# encoder.net
KiCad netlist of a schematic drawn in EAGLE
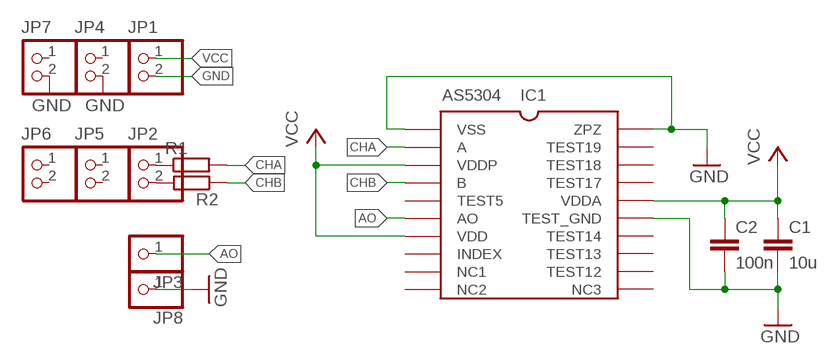
[diagram p0: schematic, sheet 1]

(export (version "E")
  (design (tool "Eeschema 10.0.6"))
  (components
    (comp (ref "C1")
      (value "10u")
      (footprint "eagle-import:C0603")
      (libsource (lib "eagle-import") (part "C-EUC0603"))
    )
    (comp (ref "C2")
      (value "100n")
      (footprint "eagle-import:C0603")
      (libsource (lib "eagle-import") (part "C-EUC0603"))
    )
    (comp (ref "IC1")
      (value "AS5304")
      (footprint "eagle-import:TSSOP20")
      (libsource (lib "eagle-import") (part "AS5304"))
    )
    (comp (ref "JP1")
      (value "PINHD_1X2_ROUND")
      (footprint "eagle-import:PINHD_1X2_ROUND")
      (libsource (lib "eagle-import") (part "PINHD_1X2_ROUND"))
    )
    (comp (ref "JP2")
      (value "PINHD_1X2_ROUND")
      (footprint "eagle-import:PINHD_1X2_ROUND")
      (libsource (lib "eagle-import") (part "PINHD_1X2_ROUND"))
    )
    (comp (ref "JP3")
      (value "PINHD-1X1")
      (footprint "eagle-import:1X01")
      (libsource (lib "eagle-import") (part "PINHD-1X1"))
    )
    (comp (ref "JP4")
      (value "PINHD_1X2_ROUND")
      (footprint "eagle-import:PINHD_1X2_ROUND")
      (libsource (lib "eagle-import") (part "PINHD_1X2_ROUND"))
    )
    (comp (ref "JP5")
      (value "PINHD_1X2_ROUND")
      (footprint "eagle-import:PINHD_1X2_ROUND")
      (libsource (lib "eagle-import") (part "PINHD_1X2_ROUND"))
    )
    (comp (ref "JP6")
      (value "PINHD_1X2_ROUND")
      (footprint "eagle-import:PINHD_1X2_ROUND")
      (libsource (lib "eagle-import") (part "PINHD_1X2_ROUND"))
    )
    (comp (ref "JP7")
      (value "PINHD_1X2_ROUND")
      (footprint "eagle-import:PINHD_1X2_ROUND")
      (libsource (lib "eagle-import") (part "PINHD_1X2_ROUND"))
    )
    (comp (ref "JP8")
      (value "PINHD-1X1")
      (footprint "eagle-import:1X01")
      (libsource (lib "eagle-import") (part "PINHD-1X1"))
    )
    (comp (ref "R1")
      (value "R-EU_R0805")
      (footprint "eagle-import:R0805")
      (libsource (lib "eagle-import") (part "R-EU_R0805"))
    )
    (comp (ref "R2")
      (value "R-EU_R0805")
      (footprint "eagle-import:R0805")
      (libsource (lib "eagle-import") (part "R-EU_R0805"))
    )
  )
  (nets
    (net (code "1") (name "AO") (class "Default")
      (node (ref "IC1") (pin "AO") (pinfunction "AO_AO") (pintype "bidirectional"))
      (node (ref "JP3") (pin "1") (pinfunction "1_1") (pintype "passive"))
    )
    (net (code "2") (name "CHA") (class "Default")
      (node (ref "IC1") (pin "A") (pinfunction "A_A") (pintype "bidirectional"))
      (node (ref "R1") (pin "2") (pinfunction "2_2") (pintype "passive"))
    )
    (net (code "3") (name "CHB") (class "Default")
      (node (ref "IC1") (pin "B") (pinfunction "B_B") (pintype "bidirectional"))
      (node (ref "R2") (pin "1") (pinfunction "1_1") (pintype "passive"))
    )
    (net (code "4") (name "GND") (class "Default")
      (node (ref "C1") (pin "2") (pinfunction "2_2") (pintype "passive"))
      (node (ref "C2") (pin "2") (pinfunction "2_2") (pintype "passive"))
      (node (ref "IC1") (pin "TEST_GND") (pinfunction "TEST_GND_TEST_GND") (pintype "bidirectional"))
      (node (ref "IC1") (pin "VSS") (pinfunction "VSS_VSS") (pintype "bidirectional"))
      (node (ref "IC1") (pin "ZPZ") (pinfunction "ZPZ_ZPZ") (pintype "bidirectional"))
      (node (ref "JP1") (pin "2") (pinfunction "2_2") (pintype "passive"))
      (node (ref "JP4") (pin "2") (pinfunction "2_2") (pintype "passive"))
      (node (ref "JP7") (pin "2") (pinfunction "2_2") (pintype "passive"))
      (node (ref "JP8") (pin "1") (pinfunction "1_1") (pintype "passive"))
    )
    (net (code "5") (name "Net-(JP2-Pad1)") (class "Default")
      (node (ref "JP2") (pin "1") (pinfunction "1_1") (pintype "passive"))
      (node (ref "R1") (pin "1") (pinfunction "1_1") (pintype "passive"))
    )
    (net (code "6") (name "Net-(JP2-Pad2)") (class "Default")
      (node (ref "JP2") (pin "2") (pinfunction "2_2") (pintype "passive"))
      (node (ref "R2") (pin "2") (pinfunction "2_2") (pintype "passive"))
    )
    (net (code "7") (name "VCC") (class "Default")
      (node (ref "C1") (pin "1") (pinfunction "1_1") (pintype "passive"))
      (node (ref "C2") (pin "1") (pinfunction "1_1") (pintype "passive"))
      (node (ref "IC1") (pin "VDD") (pinfunction "VDD_VDD") (pintype "bidirectional"))
      (node (ref "IC1") (pin "VDDA") (pinfunction "VDDA_VDDA") (pintype "bidirectional"))
      (node (ref "IC1") (pin "VDDP") (pinfunction "VDDP_VDDP") (pintype "bidirectional"))
      (node (ref "JP1") (pin "1") (pinfunction "1_1") (pintype "passive"))
    )
    (net (code "8") (name "unconnected-(IC1-NC1-PadNC)") (class "Default")
      (node (ref "IC1") (pin "NC") (pinfunction "NC1_NC") (pintype "bidirectional"))
    )
    (net (code "9") (name "unconnected-(IC1-NC2-PadNC1)") (class "Default")
      (node (ref "IC1") (pin "NC1") (pinfunction "NC2_NC1") (pintype "bidirectional"))
    )
    (net (code "10") (name "unconnected-(IC1-NC3-PadNC2)") (class "Default")
      (node (ref "IC1") (pin "NC2") (pinfunction "NC3_NC2") (pintype "bidirectional"))
    )
    (net (code "11") (name "unconnected-(IC1-PadINDEX)") (class "Default")
      (node (ref "IC1") (pin "INDEX") (pinfunction "INDEX_INDEX") (pintype "bidirectional"))
    )
    (net (code "12") (name "unconnected-(IC1-TEST5-PadTEST)") (class "Default")
      (node (ref "IC1") (pin "TEST") (pinfunction "TEST5_TEST") (pintype "bidirectional"))
    )
    (net (code "13") (name "unconnected-(IC1-TEST12-PadTEST1)") (class "Default")
      (node (ref "IC1") (pin "TEST1") (pinfunction "TEST12_TEST1") (pintype "bidirectional"))
    )
    (net (code "14") (name "unconnected-(IC1-TEST13-PadTEST2)") (class "Default")
      (node (ref "IC1") (pin "TEST2") (pinfunction "TEST13_TEST2") (pintype "bidirectional"))
    )
    (net (code "15") (name "unconnected-(IC1-TEST14-PadTEST3)") (class "Default")
      (node (ref "IC1") (pin "TEST3") (pinfunction "TEST14_TEST3") (pintype "bidirectional"))
    )
    (net (code "16") (name "unconnected-(IC1-TEST17-PadTEST4)") (class "Default")
      (node (ref "IC1") (pin "TEST4") (pinfunction "TEST17_TEST4") (pintype "bidirectional"))
    )
    (net (code "17") (name "unconnected-(IC1-TEST18-PadTEST5)") (class "Default")
      (node (ref "IC1") (pin "TEST5") (pinfunction "TEST18_TEST5") (pintype "bidirectional"))
    )
    (net (code "18") (name "unconnected-(IC1-TEST19-PadTEST6)") (class "Default")
      (node (ref "IC1") (pin "TEST6") (pinfunction "TEST19_TEST6") (pintype "bidirectional"))
    )
    (net (code "19") (name "unconnected-(JP4-Pad1)") (class "Default")
      (node (ref "JP4") (pin "1") (pinfunction "1_1") (pintype "passive"))
    )
    (net (code "20") (name "unconnected-(JP5-Pad1)") (class "Default")
      (node (ref "JP5") (pin "1") (pinfunction "1_1") (pintype "passive"))
    )
    (net (code "21") (name "unconnected-(JP5-Pad2)") (class "Default")
      (node (ref "JP5") (pin "2") (pinfunction "2_2") (pintype "passive"))
    )
    (net (code "22") (name "unconnected-(JP6-Pad1)") (class "Default")
      (node (ref "JP6") (pin "1") (pinfunction "1_1") (pintype "passive"))
    )
    (net (code "23") (name "unconnected-(JP6-Pad2)") (class "Default")
      (node (ref "JP6") (pin "2") (pinfunction "2_2") (pintype "passive"))
    )
    (net (code "24") (name "unconnected-(JP7-Pad1)") (class "Default")
      (node (ref "JP7") (pin "1") (pinfunction "1_1") (pintype "passive"))
    )
  )
)
